# Leds_and_Buttons.net
KiCad netlist of a schematic drawn in Altium Designer
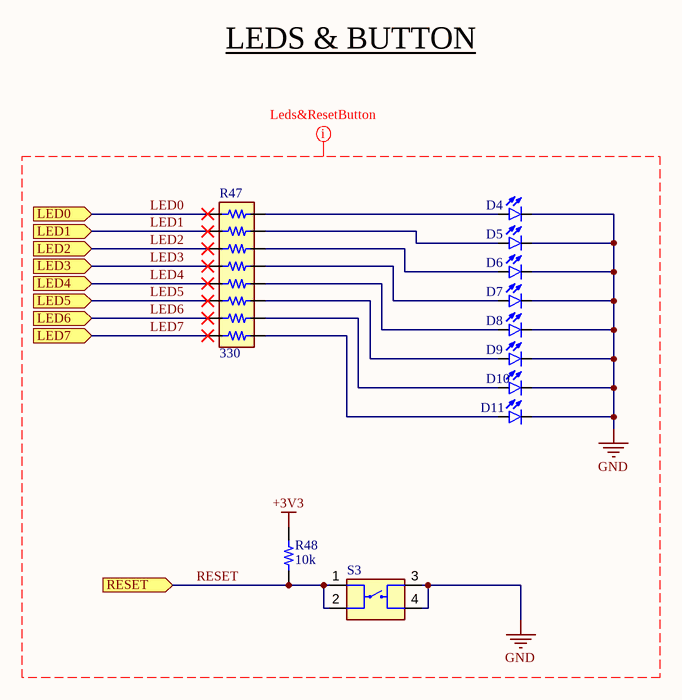
[diagram p0: Leds_and_Buttons.SchDoc]

(export (version "E")
  (design (tool "Eeschema 10.0.6"))
  (components
    (comp (ref "D4")
      (value "597-3305-607F")
      (footprint "0603_LED")
      (description "LED blue diffused 0603 SMD")
      (fields (field (name "MANUFACTURER") "Würth Elektronik") (field (name "PARTNUMBER") "150060BS55040"))
      (libsource (lib "Integrated_Circuits") (part "LED_BLUE_0603"))
    )
    (comp (ref "D5")
      (value "597-3305-607F")
      (footprint "0603_LED")
      (description "LED blue diffused 0603 SMD")
      (fields (field (name "MANUFACTURER") "Würth Elektronik") (field (name "PARTNUMBER") "150060BS55040"))
      (libsource (lib "Integrated_Circuits") (part "LED_BLUE_0603"))
    )
    (comp (ref "D6")
      (value "597-3305-607F")
      (footprint "0603_LED")
      (description "LED blue diffused 0603 SMD")
      (fields (field (name "MANUFACTURER") "Würth Elektronik") (field (name "PARTNUMBER") "150060BS55040"))
      (libsource (lib "Integrated_Circuits") (part "LED_BLUE_0603"))
    )
    (comp (ref "D7")
      (value "597-3305-607F")
      (footprint "0603_LED")
      (description "LED blue diffused 0603 SMD")
      (fields (field (name "MANUFACTURER") "Würth Elektronik") (field (name "PARTNUMBER") "150060BS55040"))
      (libsource (lib "Integrated_Circuits") (part "LED_BLUE_0603"))
    )
    (comp (ref "D8")
      (value "597-3305-607F")
      (footprint "0603_LED")
      (description "LED blue diffused 0603 SMD")
      (fields (field (name "MANUFACTURER") "Würth Elektronik") (field (name "PARTNUMBER") "150060BS55040"))
      (libsource (lib "Integrated_Circuits") (part "LED_BLUE_0603"))
    )
    (comp (ref "D9")
      (value "597-3305-607F")
      (footprint "0603_LED")
      (description "LED blue diffused 0603 SMD")
      (fields (field (name "MANUFACTURER") "Würth Elektronik") (field (name "PARTNUMBER") "150060BS55040"))
      (libsource (lib "Integrated_Circuits") (part "LED_BLUE_0603"))
    )
    (comp (ref "D10")
      (value "597-3305-607F")
      (footprint "0603_LED")
      (description "LED blue diffused 0603 SMD")
      (fields (field (name "MANUFACTURER") "Würth Elektronik") (field (name "PARTNUMBER") "150060BS55040"))
      (libsource (lib "Integrated_Circuits") (part "LED_BLUE_0603"))
    )
    (comp (ref "D11")
      (value "597-3305-607F")
      (footprint "0603_LED")
      (description "LED blue diffused 0603 SMD")
      (fields (field (name "MANUFACTURER") "Würth Elektronik") (field (name "PARTNUMBER") "150060BS55040"))
      (libsource (lib "Integrated_Circuits") (part "LED_BLUE_0603"))
    )
    (comp (ref "R47")
      (value "330")
      (footprint "ArrayResistor-1506")
      (description "RES ARRAY 8 RES 330 OHM 1506")
      (fields (field (name "MANUFACTURER") "Panasonic") (field (name "PARTNUMBER") "EXB-2HV331JV"))
      (libsource (lib "Pasivos") (part "EXB-2HV331JV"))
    )
    (comp (ref "R48")
      (value "10k")
      (footprint "RES0402")
      (description "RES SMD 10K OHM 1% 0.063W 0402")
      (fields (field (name "TOLERANCE") "1%") (field (name "PARTNUMBER") "CRCW040210K0FK"))
      (libsource (lib "Pasivos") (part "CRCW040210K0FK"))
    )
    (comp (ref "S3")
      (value "PTS526SK15SMTR2 LFS")
      (footprint "Push Button")
      (description "SWITCH TACTILE, SPST-NO, 0.05A, 12V")
      (fields (field (name "MANUFACTURER") "C&K"))
      (libsource (lib "Pasivos") (part "PTS526 SK15 SMTR2 LFS"))
    )
  )
  (nets
    (net (code "1") (name "+3V3") (class "Default")
      (node (ref "R48") (pin "2") (pinfunction "2_2") (pintype "passive"))
    )
    (net (code "2") (name "/LED0") (class "Default")
      (node (ref "R47") (pin "1") (pinfunction "1_1") (pintype "passive+no_connect"))
    )
    (net (code "3") (name "/LED1") (class "Default")
      (node (ref "R47") (pin "2") (pinfunction "2_2") (pintype "passive+no_connect"))
    )
    (net (code "4") (name "/LED2") (class "Default")
      (node (ref "R47") (pin "3") (pinfunction "3_3") (pintype "passive+no_connect"))
    )
    (net (code "5") (name "/LED3") (class "Default")
      (node (ref "R47") (pin "4") (pinfunction "4_4") (pintype "passive+no_connect"))
    )
    (net (code "6") (name "/LED4") (class "Default")
      (node (ref "R47") (pin "5") (pinfunction "5_5") (pintype "passive+no_connect"))
    )
    (net (code "7") (name "/LED5") (class "Default")
      (node (ref "R47") (pin "6") (pinfunction "6_6") (pintype "passive+no_connect"))
    )
    (net (code "8") (name "/LED6") (class "Default")
      (node (ref "R47") (pin "7") (pinfunction "7_7") (pintype "passive+no_connect"))
    )
    (net (code "9") (name "/LED7") (class "Default")
      (node (ref "R47") (pin "8") (pinfunction "8_8") (pintype "passive+no_connect"))
    )
    (net (code "10") (name "/RESET") (class "Default")
      (node (ref "R48") (pin "1") (pinfunction "1_1") (pintype "passive"))
      (node (ref "S3") (pin "1") (pinfunction "1_1") (pintype "passive"))
      (node (ref "S3") (pin "2") (pinfunction "2_2") (pintype "passive"))
    )
    (net (code "11") (name "GND") (class "Default")
      (node (ref "D10") (pin "C") (pinfunction "C_C") (pintype "passive"))
      (node (ref "D11") (pin "C") (pinfunction "C_C") (pintype "passive"))
      (node (ref "D4") (pin "C") (pinfunction "C_C") (pintype "passive"))
      (node (ref "D5") (pin "C") (pinfunction "C_C") (pintype "passive"))
      (node (ref "D6") (pin "C") (pinfunction "C_C") (pintype "passive"))
      (node (ref "D7") (pin "C") (pinfunction "C_C") (pintype "passive"))
      (node (ref "D8") (pin "C") (pinfunction "C_C") (pintype "passive"))
      (node (ref "D9") (pin "C") (pinfunction "C_C") (pintype "passive"))
      (node (ref "S3") (pin "3") (pinfunction "3_3") (pintype "passive"))
      (node (ref "S3") (pin "4") (pinfunction "4_4") (pintype "passive"))
    )
    (net (code "12") (name "Net-(D4-PadA)") (class "Default")
      (node (ref "D4") (pin "A") (pinfunction "A_A") (pintype "passive"))
      (node (ref "R47") (pin "16") (pinfunction "16_16") (pintype "passive"))
    )
    (net (code "13") (name "Net-(D5-PadA)") (class "Default")
      (node (ref "D5") (pin "A") (pinfunction "A_A") (pintype "passive"))
      (node (ref "R47") (pin "15") (pinfunction "15_15") (pintype "passive"))
    )
    (net (code "14") (name "Net-(D6-PadA)") (class "Default")
      (node (ref "D6") (pin "A") (pinfunction "A_A") (pintype "passive"))
      (node (ref "R47") (pin "14") (pinfunction "14_14") (pintype "passive"))
    )
    (net (code "15") (name "Net-(D7-PadA)") (class "Default")
      (node (ref "D7") (pin "A") (pinfunction "A_A") (pintype "passive"))
      (node (ref "R47") (pin "13") (pinfunction "13_13") (pintype "passive"))
    )
    (net (code "16") (name "Net-(D8-PadA)") (class "Default")
      (node (ref "D8") (pin "A") (pinfunction "A_A") (pintype "passive"))
      (node (ref "R47") (pin "12") (pinfunction "12_12") (pintype "passive"))
    )
    (net (code "17") (name "Net-(D9-PadA)") (class "Default")
      (node (ref "D9") (pin "A") (pinfunction "A_A") (pintype "passive"))
      (node (ref "R47") (pin "11") (pinfunction "11_11") (pintype "passive"))
    )
    (net (code "18") (name "Net-(D10-PadA)") (class "Default")
      (node (ref "D10") (pin "A") (pinfunction "A_A") (pintype "passive"))
      (node (ref "R47") (pin "10") (pinfunction "10_10") (pintype "passive"))
    )
    (net (code "19") (name "Net-(D11-PadA)") (class "Default")
      (node (ref "D11") (pin "A") (pinfunction "A_A") (pintype "passive"))
      (node (ref "R47") (pin "9") (pinfunction "9_9") (pintype "passive"))
    )
  )
)
